# rapidshark-lipo-sensor-mk-3_7.net
KiCad netlist of a schematic drawn in EAGLE
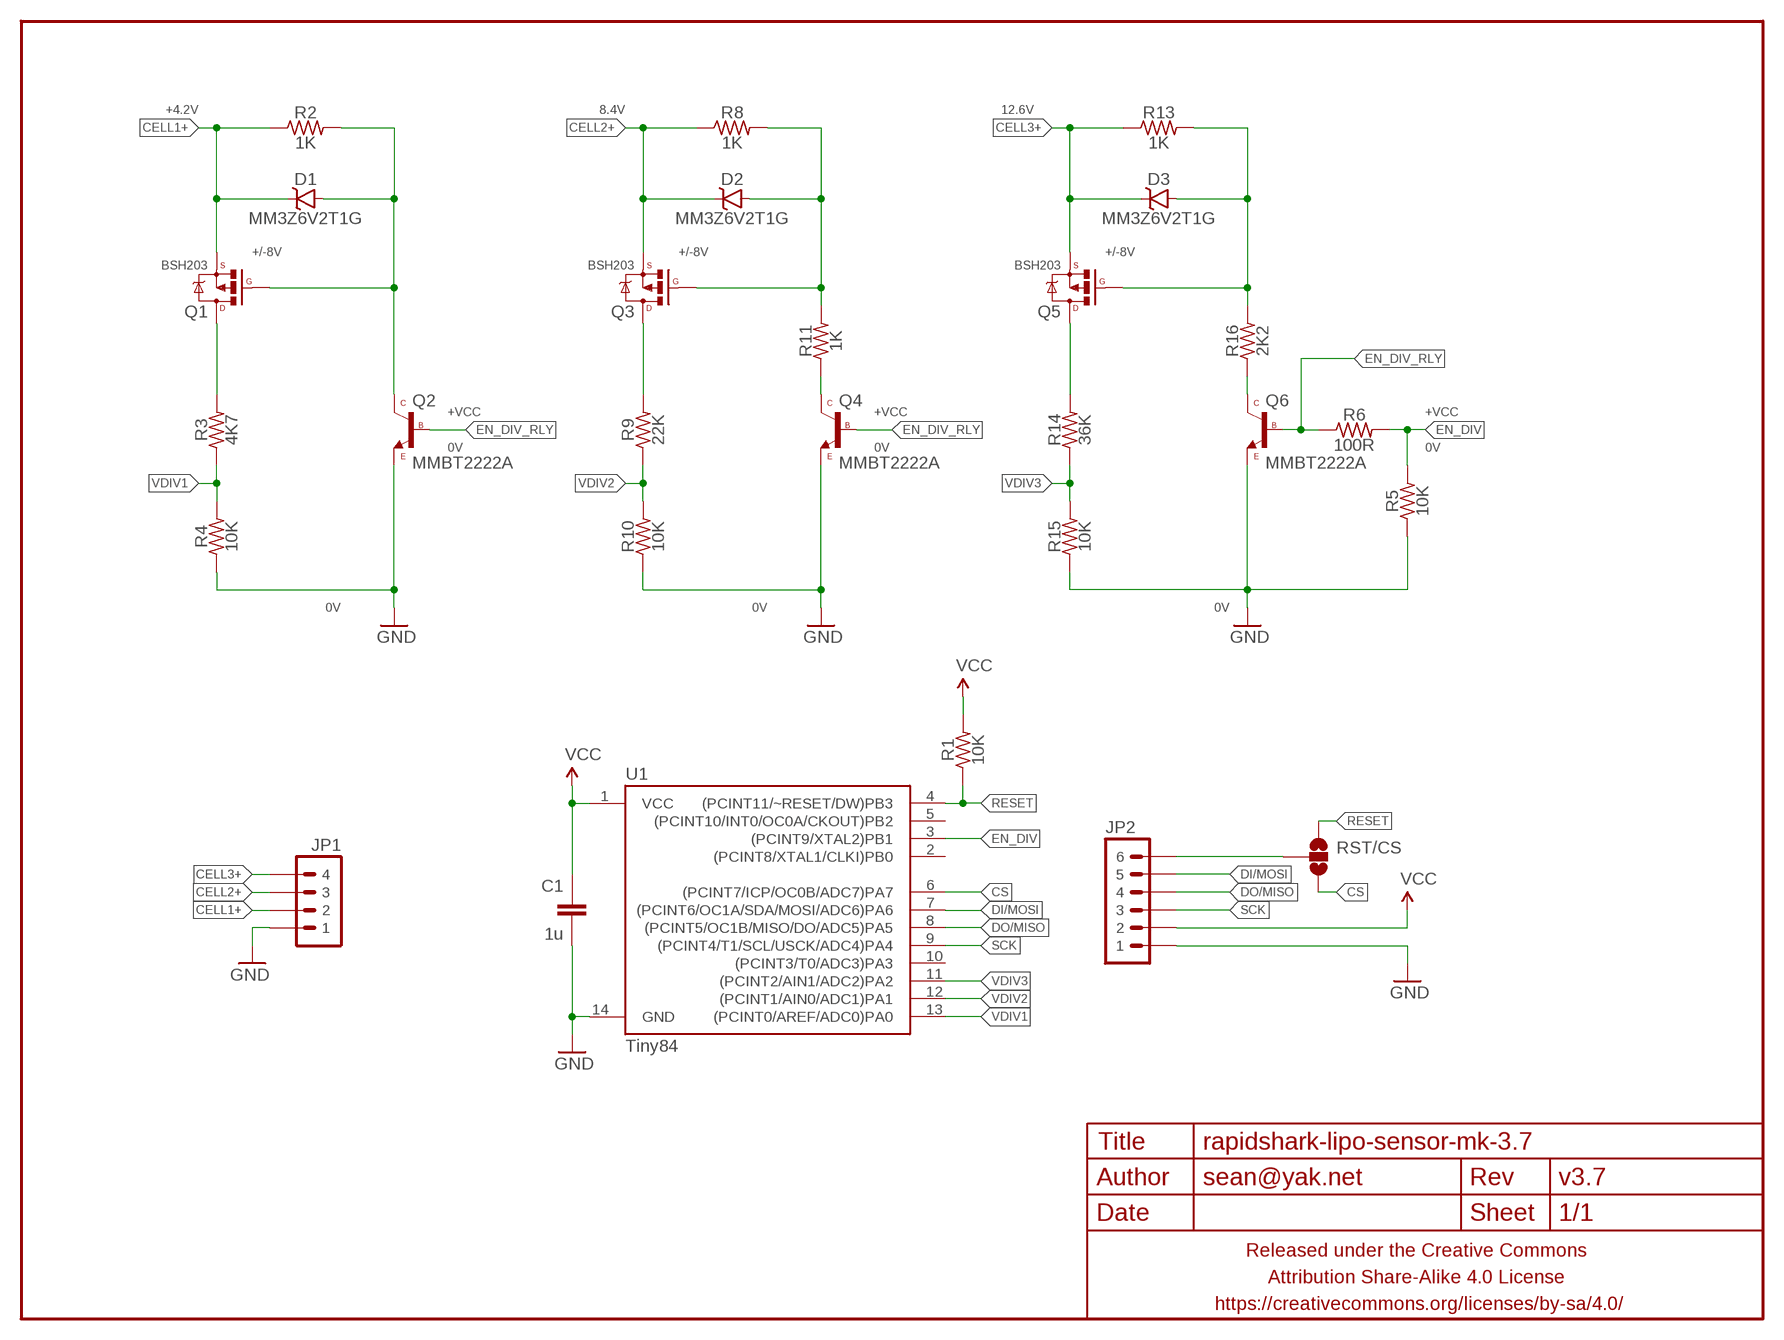
[diagram p0: schematic, sheet 1]

(export (version "E")
  (design (tool "Eeschema 10.0.6"))
  (components
    (comp (ref "C1")
      (value "1u")
      (footprint "eagle-import:C0603-TIGHTER")
      (libsource (lib "eagle-import") (part "CAPACITOR-CERAMICC0603-TIGHTER"))
    )
    (comp (ref "D1")
      (value "MM3Z6V2T1G")
      (footprint "eagle-import:SOD323-ZENNER")
      (libsource (lib "eagle-import") (part "DIODE-ZENERSOD323"))
    )
    (comp (ref "D2")
      (value "MM3Z6V2T1G")
      (footprint "eagle-import:SOD323-ZENNER")
      (libsource (lib "eagle-import") (part "DIODE-ZENERSOD323"))
    )
    (comp (ref "D3")
      (value "MM3Z6V2T1G")
      (footprint "eagle-import:SOD323-ZENNER")
      (libsource (lib "eagle-import") (part "DIODE-ZENERSOD323"))
    )
    (comp (ref "FRAME1")
      (value "FRAME-LETTERNO_PACKAGE")
      (footprint "eagle-import:DUMMY")
      (fields (field (name "DESIGNER") "sean@yak.net") (field (name "VERSION") "v3.7"))
      (libsource (lib "eagle-import") (part "FRAME-LETTERNO_PACKAGE"))
    )
    (comp (ref "JP1")
      (value "M04JST_XH_RA")
      (footprint "eagle-import:JST-4-XH-RA-PTH")
      (libsource (lib "eagle-import") (part "M04JST_XH_RA"))
    )
    (comp (ref "JP2")
      (value "M06PTH_CENTERED")
      (footprint "eagle-import:1X06_CENTERED")
      (libsource (lib "eagle-import") (part "M06PTH_CENTERED"))
    )
    (comp (ref "Q1")
      (value "BSH203")
      (footprint "eagle-import:SOT23")
      (libsource (lib "eagle-import") (part "MOSFET-PCHANNELSOT-23"))
    )
    (comp (ref "Q2")
      (value "MMBT2222A")
      (footprint "eagle-import:SOT23")
      (libsource (lib "eagle-import") (part "TRANSISTOR_NPNMMBT2222A"))
    )
    (comp (ref "Q3")
      (value "BSH203")
      (footprint "eagle-import:SOT23")
      (libsource (lib "eagle-import") (part "MOSFET-PCHANNELSOT-23"))
    )
    (comp (ref "Q4")
      (value "MMBT2222A")
      (footprint "eagle-import:SOT23")
      (libsource (lib "eagle-import") (part "TRANSISTOR_NPNMMBT2222A"))
    )
    (comp (ref "Q5")
      (value "BSH203")
      (footprint "eagle-import:SOT23")
      (libsource (lib "eagle-import") (part "MOSFET-PCHANNELSOT-23"))
    )
    (comp (ref "Q6")
      (value "MMBT2222A")
      (footprint "eagle-import:SOT23")
      (libsource (lib "eagle-import") (part "TRANSISTOR_NPNMMBT2222A"))
    )
    (comp (ref "R1")
      (value "10K")
      (footprint "eagle-import:R0603-TIGHTER")
      (libsource (lib "eagle-import") (part "RESISTORR0603-TIGHTER"))
    )
    (comp (ref "R2")
      (value "1K")
      (footprint "eagle-import:R0603-TIGHTER")
      (libsource (lib "eagle-import") (part "RESISTORR0603-TIGHTER"))
    )
    (comp (ref "R3")
      (value "4K7")
      (footprint "eagle-import:R0603-TIGHTER")
      (libsource (lib "eagle-import") (part "RESISTORR0603-TIGHTER"))
    )
    (comp (ref "R4")
      (value "10K")
      (footprint "eagle-import:R0603-TIGHTER")
      (libsource (lib "eagle-import") (part "RESISTORR0603-TIGHTER"))
    )
    (comp (ref "R5")
      (value "10K")
      (footprint "eagle-import:R0603-TIGHTER")
      (libsource (lib "eagle-import") (part "RESISTORR0603-TIGHTER"))
    )
    (comp (ref "R6")
      (value "100R")
      (footprint "eagle-import:R0603-TIGHTER")
      (libsource (lib "eagle-import") (part "RESISTORR0603-TIGHTER"))
    )
    (comp (ref "R8")
      (value "1K")
      (footprint "eagle-import:R0603-TIGHTER")
      (libsource (lib "eagle-import") (part "RESISTORR0603-TIGHTER"))
    )
    (comp (ref "R9")
      (value "22K")
      (footprint "eagle-import:R0603-TIGHTER")
      (libsource (lib "eagle-import") (part "RESISTORR0603-TIGHTER"))
    )
    (comp (ref "R10")
      (value "10K")
      (footprint "eagle-import:R0603-TIGHTER")
      (libsource (lib "eagle-import") (part "RESISTORR0603-TIGHTER"))
    )
    (comp (ref "R11")
      (value "1K")
      (footprint "eagle-import:R0603-TIGHTER")
      (libsource (lib "eagle-import") (part "RESISTORR0603-TIGHTER"))
    )
    (comp (ref "R13")
      (value "1K")
      (footprint "eagle-import:R0603-TIGHTER")
      (libsource (lib "eagle-import") (part "RESISTORR0603-TIGHTER"))
    )
    (comp (ref "R14")
      (value "36K")
      (footprint "eagle-import:R0603-TIGHTER")
      (libsource (lib "eagle-import") (part "RESISTORR0603-TIGHTER"))
    )
    (comp (ref "R15")
      (value "10K")
      (footprint "eagle-import:R0603-TIGHTER")
      (libsource (lib "eagle-import") (part "RESISTORR0603-TIGHTER"))
    )
    (comp (ref "R16")
      (value "2K2")
      (footprint "eagle-import:R0603-TIGHTER")
      (libsource (lib "eagle-import") (part "RESISTORR0603-TIGHTER"))
    )
    (comp (ref "RST/CS")
      (value "JUMPER-PAD-3-NOFULL_BOX_SILK")
      (footprint "eagle-import:PAD-JUMPER-3-NO_YES_SILK_FULL_BOX")
      (libsource (lib "eagle-import") (part "JUMPER-PAD-3-NOFULL_BOX_SILK"))
    )
    (comp (ref "U1")
      (value "Tiny84")
      (footprint "eagle-import:SO14")
      (libsource (lib "eagle-import") (part "ATTINY84"))
    )
  )
  (nets
    (net (code "1") (name "CELL1+") (class "Default")
      (node (ref "D1") (pin "C") (pinfunction "C_C") (pintype "passive"))
      (node (ref "JP1") (pin "2") (pinfunction "2_2") (pintype "passive"))
      (node (ref "Q1") (pin "2") (pinfunction "S_2") (pintype "passive"))
      (node (ref "R2") (pin "1") (pinfunction "1_1") (pintype "passive"))
    )
    (net (code "2") (name "CELL2+") (class "Default")
      (node (ref "D2") (pin "C") (pinfunction "C_C") (pintype "passive"))
      (node (ref "JP1") (pin "3") (pinfunction "3_3") (pintype "passive"))
      (node (ref "Q3") (pin "2") (pinfunction "S_2") (pintype "passive"))
      (node (ref "R8") (pin "1") (pinfunction "1_1") (pintype "passive"))
    )
    (net (code "3") (name "CELL3+") (class "Default")
      (node (ref "D3") (pin "C") (pinfunction "C_C") (pintype "passive"))
      (node (ref "JP1") (pin "4") (pinfunction "4_4") (pintype "passive"))
      (node (ref "Q5") (pin "2") (pinfunction "S_2") (pintype "passive"))
      (node (ref "R13") (pin "1") (pinfunction "1_1") (pintype "passive"))
    )
    (net (code "4") (name "CS") (class "Default")
      (node (ref "RST/CS") (pin "3") (pinfunction "3_3") (pintype "passive"))
      (node (ref "U1") (pin "6") (pinfunction "(PCINT7/ICP/OC0B/ADC7)PA7_6") (pintype "bidirectional"))
    )
    (net (code "5") (name "DI{slash}MOSI") (class "Default")
      (node (ref "JP2") (pin "5") (pinfunction "5_5") (pintype "passive"))
      (node (ref "U1") (pin "7") (pinfunction "(PCINT6/OC1A/SDA/MOSI/ADC6)PA6_7") (pintype "bidirectional"))
    )
    (net (code "6") (name "DO{slash}MISO") (class "Default")
      (node (ref "JP2") (pin "4") (pinfunction "4_4") (pintype "passive"))
      (node (ref "U1") (pin "8") (pinfunction "(PCINT5/OC1B/MISO/DO/ADC5)PA5_8") (pintype "bidirectional"))
    )
    (net (code "7") (name "EN_DIV") (class "Default")
      (node (ref "R5") (pin "2") (pinfunction "2_2") (pintype "passive"))
      (node (ref "R6") (pin "2") (pinfunction "2_2") (pintype "passive"))
      (node (ref "U1") (pin "3") (pinfunction "(PCINT9/XTAL2)PB1_3") (pintype "bidirectional"))
    )
    (net (code "8") (name "EN_DIV_RLY") (class "Default")
      (node (ref "Q2") (pin "1") (pinfunction "B_1") (pintype "passive"))
      (node (ref "Q4") (pin "1") (pinfunction "B_1") (pintype "passive"))
      (node (ref "Q6") (pin "1") (pinfunction "B_1") (pintype "passive"))
      (node (ref "R6") (pin "1") (pinfunction "1_1") (pintype "passive"))
    )
    (net (code "9") (name "GND") (class "Default")
      (node (ref "C1") (pin "2") (pinfunction "2_2") (pintype "passive"))
      (node (ref "JP1") (pin "1") (pinfunction "1_1") (pintype "passive"))
      (node (ref "JP2") (pin "1") (pinfunction "1_1") (pintype "passive"))
      (node (ref "Q2") (pin "2") (pinfunction "E_2") (pintype "passive"))
      (node (ref "Q4") (pin "2") (pinfunction "E_2") (pintype "passive"))
      (node (ref "Q6") (pin "2") (pinfunction "E_2") (pintype "passive"))
      (node (ref "R10") (pin "1") (pinfunction "1_1") (pintype "passive"))
      (node (ref "R15") (pin "1") (pinfunction "1_1") (pintype "passive"))
      (node (ref "R4") (pin "1") (pinfunction "1_1") (pintype "passive"))
      (node (ref "R5") (pin "1") (pinfunction "1_1") (pintype "passive"))
      (node (ref "U1") (pin "14") (pinfunction "GND_14") (pintype "bidirectional"))
    )
    (net (code "10") (name "Net-(JP2-Pad6)") (class "Default")
      (node (ref "JP2") (pin "6") (pinfunction "6_6") (pintype "passive"))
      (node (ref "RST/CS") (pin "2") (pinfunction "2_2") (pintype "passive"))
    )
    (net (code "11") (name "Net-(Q1-D)") (class "Default")
      (node (ref "Q1") (pin "3") (pinfunction "D_3") (pintype "passive"))
      (node (ref "R3") (pin "2") (pinfunction "2_2") (pintype "passive"))
    )
    (net (code "12") (name "Net-(Q1-G)") (class "Default")
      (node (ref "D1") (pin "A") (pinfunction "A_A") (pintype "passive"))
      (node (ref "Q1") (pin "1") (pinfunction "G_1") (pintype "passive"))
      (node (ref "Q2") (pin "3") (pinfunction "C_3") (pintype "passive"))
      (node (ref "R2") (pin "2") (pinfunction "2_2") (pintype "passive"))
    )
    (net (code "13") (name "Net-(Q3-D)") (class "Default")
      (node (ref "Q3") (pin "3") (pinfunction "D_3") (pintype "passive"))
      (node (ref "R9") (pin "2") (pinfunction "2_2") (pintype "passive"))
    )
    (net (code "14") (name "Net-(Q3-G)") (class "Default")
      (node (ref "D2") (pin "A") (pinfunction "A_A") (pintype "passive"))
      (node (ref "Q3") (pin "1") (pinfunction "G_1") (pintype "passive"))
      (node (ref "R11") (pin "2") (pinfunction "2_2") (pintype "passive"))
      (node (ref "R8") (pin "2") (pinfunction "2_2") (pintype "passive"))
    )
    (net (code "15") (name "Net-(Q4-C)") (class "Default")
      (node (ref "Q4") (pin "3") (pinfunction "C_3") (pintype "passive"))
      (node (ref "R11") (pin "1") (pinfunction "1_1") (pintype "passive"))
    )
    (net (code "16") (name "Net-(Q5-D)") (class "Default")
      (node (ref "Q5") (pin "3") (pinfunction "D_3") (pintype "passive"))
      (node (ref "R14") (pin "2") (pinfunction "2_2") (pintype "passive"))
    )
    (net (code "17") (name "Net-(Q5-G)") (class "Default")
      (node (ref "D3") (pin "A") (pinfunction "A_A") (pintype "passive"))
      (node (ref "Q5") (pin "1") (pinfunction "G_1") (pintype "passive"))
      (node (ref "R13") (pin "2") (pinfunction "2_2") (pintype "passive"))
      (node (ref "R16") (pin "2") (pinfunction "2_2") (pintype "passive"))
    )
    (net (code "18") (name "Net-(Q6-C)") (class "Default")
      (node (ref "Q6") (pin "3") (pinfunction "C_3") (pintype "passive"))
      (node (ref "R16") (pin "1") (pinfunction "1_1") (pintype "passive"))
    )
    (net (code "19") (name "RESET") (class "Default")
      (node (ref "R1") (pin "1") (pinfunction "1_1") (pintype "passive"))
      (node (ref "RST/CS") (pin "1") (pinfunction "1_1") (pintype "passive"))
      (node (ref "U1") (pin "4") (pinfunction "(PCINT11/~{RESET/DW})PB3_4") (pintype "bidirectional"))
    )
    (net (code "20") (name "SCK") (class "Default")
      (node (ref "JP2") (pin "3") (pinfunction "3_3") (pintype "passive"))
      (node (ref "U1") (pin "9") (pinfunction "(PCINT4/T1/SCL/USCK/ADC4)PA4_9") (pintype "bidirectional"))
    )
    (net (code "21") (name "VCC") (class "Default")
      (node (ref "C1") (pin "1") (pinfunction "1_1") (pintype "passive"))
      (node (ref "JP2") (pin "2") (pinfunction "2_2") (pintype "passive"))
      (node (ref "R1") (pin "2") (pinfunction "2_2") (pintype "passive"))
      (node (ref "U1") (pin "1") (pinfunction "VCC_1") (pintype "bidirectional"))
    )
    (net (code "22") (name "VDIV1") (class "Default")
      (node (ref "R3") (pin "1") (pinfunction "1_1") (pintype "passive"))
      (node (ref "R4") (pin "2") (pinfunction "2_2") (pintype "passive"))
      (node (ref "U1") (pin "13") (pinfunction "(PCINT0/AREF/ADC0)PA0_13") (pintype "bidirectional"))
    )
    (net (code "23") (name "VDIV2") (class "Default")
      (node (ref "R10") (pin "2") (pinfunction "2_2") (pintype "passive"))
      (node (ref "R9") (pin "1") (pinfunction "1_1") (pintype "passive"))
      (node (ref "U1") (pin "12") (pinfunction "(PCINT1/AIN0/ADC1)PA1_12") (pintype "bidirectional"))
    )
    (net (code "24") (name "VDIV3") (class "Default")
      (node (ref "R14") (pin "1") (pinfunction "1_1") (pintype "passive"))
      (node (ref "R15") (pin "2") (pinfunction "2_2") (pintype "passive"))
      (node (ref "U1") (pin "11") (pinfunction "(PCINT2/AIN1/ADC2)PA2_11") (pintype "bidirectional"))
    )
    (net (code "25") (name "unconnected-(U1-(PCINT3{slash}T0{slash}ADC3)PA3-Pad10)") (class "Default")
      (node (ref "U1") (pin "10") (pinfunction "(PCINT3/T0/ADC3)PA3_10") (pintype "bidirectional"))
    )
    (net (code "26") (name "unconnected-(U1-(PCINT8{slash}XTAL1{slash}CLKI)PB0-Pad2)") (class "Default")
      (node (ref "U1") (pin "2") (pinfunction "(PCINT8/XTAL1/CLKI)PB0_2") (pintype "bidirectional"))
    )
    (net (code "27") (name "unconnected-(U1-(PCINT10{slash}INT0{slash}OC0A{slash}CKOUT)PB2-Pad5)") (class "Default")
      (node (ref "U1") (pin "5") (pinfunction "(PCINT10/INT0/OC0A/CKOUT)PB2_5") (pintype "bidirectional"))
    )
  )
)
